# 004-H-01.net
KiCad netlist of a schematic drawn in Altium Designer
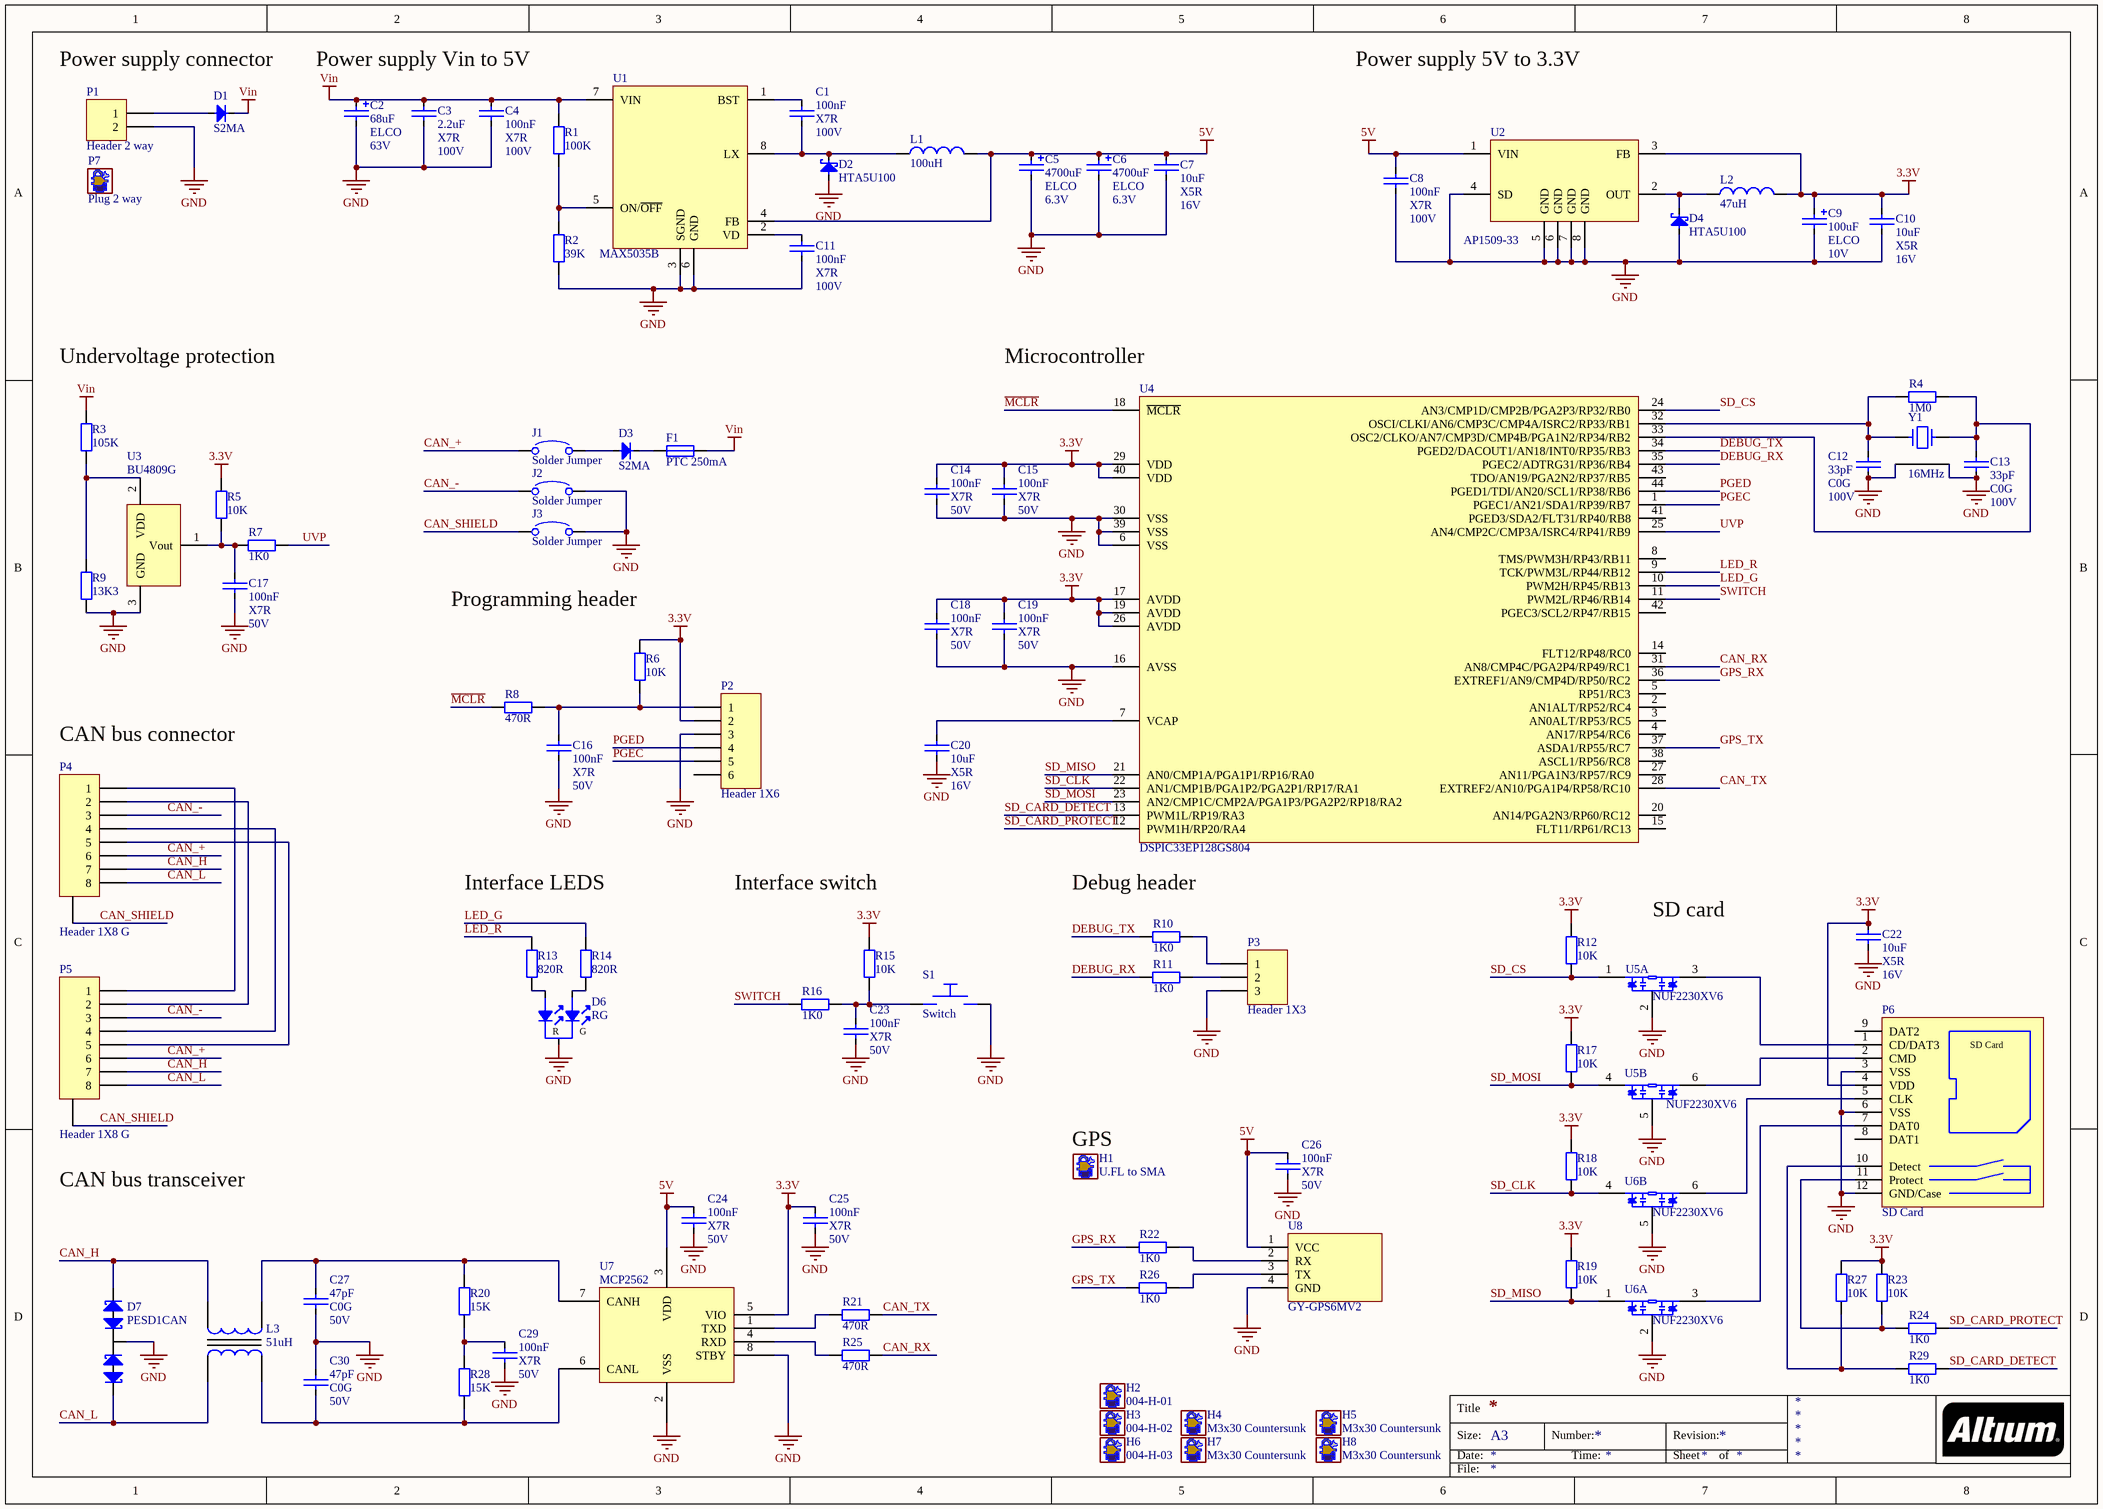
[diagram p0: 004-H-01.SchDoc]

(export (version "E")
  (design (tool "Eeschema 10.0.6"))
  (components
    (comp (ref "C1")
      (value "100nF")
      (footprint "CAP0805")
      (description "Capacitor")
      (fields (field (name "DIELECTRIC") "X7R") (field (name "VOLTAGERATING") "100V"))
      (libsource (lib "004-H-01") (part "Capacitor"))
    )
    (comp (ref "C2")
      (value "68uF")
      (footprint "CAPP8383X62N")
      (description "Capacitor Pol")
      (fields
        (field (name "MANUFACTURER") "Panasonic")
        (field (name "MANUFACTURER PART NO") "EEEFK1J680UP")
        (field (name "DIELECTRIC") "ELCO")
        (field (name "VOLTAGERATING") "63V")
      )
      (libsource (lib "004-H-01") (part "CapacitorPol"))
    )
    (comp (ref "C3")
      (value "2.2uF")
      (footprint "CAP1210")
      (description "Capacitor")
      (fields
        (field (name "MANUFACTURER") "AVX")
        (field (name "MANUFACTURER PART NO") "C1210X225K1RACTU")
        (field (name "DIELECTRIC") "X7R")
        (field (name "VOLTAGERATING") "100V")
      )
      (libsource (lib "ProtoBoard") (part "Capacitor"))
    )
    (comp (ref "C4")
      (value "100nF")
      (footprint "CAP0805")
      (description "Capacitor")
      (fields (field (name "DIELECTRIC") "X7R") (field (name "VOLTAGERATING") "100V"))
      (libsource (lib "ProtoBoard") (part "Capacitor"))
    )
    (comp (ref "C5")
      (value "4700uF")
      (footprint "CAPPOL_leaded_D12_5L20P5")
      (description "Capacitor Pol")
      (fields
        (field (name "MANUFACTURER") "Panasonic")
        (field (name "MANUFACTURER PART NO") "ECA0JM472")
        (field (name "DIELECTRIC") "ELCO")
        (field (name "VOLTAGERATING") "6.3V")
      )
      (libsource (lib "004-H-01") (part "CapacitorPol"))
    )
    (comp (ref "C6")
      (value "4700uF")
      (footprint "CAPPOL_leaded_D12_5L20P5")
      (description "Capacitor Pol")
      (fields
        (field (name "MANUFACTURER") "Panasonic")
        (field (name "MANUFACTURER PART NO") "ECA0JM472")
        (field (name "DIELECTRIC") "ELCO")
        (field (name "VOLTAGERATING") "6.3V")
      )
      (libsource (lib "004-H-01") (part "CapacitorPol"))
    )
    (comp (ref "C7")
      (value "10uF")
      (footprint "CAP1210")
      (description "Capacitor")
      (fields
        (field (name "MANUFACTURER") "Multicomp")
        (field (name "MANUFACTURER PART NO") "MC1210X106K160CT")
        (field (name "DIELECTRIC") "X5R")
        (field (name "VOLTAGERATING") "16V")
      )
      (libsource (lib "ProtoBoard") (part "Capacitor"))
    )
    (comp (ref "C8")
      (value "100nF")
      (footprint "CAP0805")
      (description "Capacitor")
      (fields (field (name "DIELECTRIC") "X7R") (field (name "VOLTAGERATING") "100V"))
      (libsource (lib "004-H-01") (part "Capacitor"))
    )
    (comp (ref "C9")
      (value "100uF")
      (footprint "CAPP8383X62N")
      (description "Capacitor Pol")
      (fields
        (field (name "MANUFACTURER") "Panasonic")
        (field (name "MANUFACTURER PART NO") "EEEHA1A101P")
        (field (name "DIELECTRIC") "ELCO")
        (field (name "VOLTAGERATING") "10V")
      )
      (libsource (lib "004-H-01") (part "CapacitorPol"))
    )
    (comp (ref "C10")
      (value "10uF")
      (footprint "CAP1210")
      (description "Capacitor")
      (fields
        (field (name "MANUFACTURER") "Multicomp")
        (field (name "MANUFACTURER PART NO") "MC1210X106K160CT")
        (field (name "DIELECTRIC") "X5R")
        (field (name "VOLTAGERATING") "16V")
      )
      (libsource (lib "ProtoBoard") (part "Capacitor"))
    )
    (comp (ref "C11")
      (value "100nF")
      (footprint "CAP0805")
      (description "Capacitor")
      (fields (field (name "DIELECTRIC") "X7R") (field (name "VOLTAGERATING") "100V"))
      (libsource (lib "004-H-01") (part "Capacitor"))
    )
    (comp (ref "C12")
      (value "33pF")
      (footprint "CAP0603")
      (description "Capacitor")
      (fields (field (name "DIELECTRIC") "C0G") (field (name "VOLTAGERATING") "100V"))
      (libsource (lib "ProtoBoard") (part "Capacitor"))
    )
    (comp (ref "C13")
      (value "33pF")
      (footprint "CAP0603")
      (description "Capacitor")
      (fields (field (name "DIELECTRIC") "C0G") (field (name "VOLTAGERATING") "100V"))
      (libsource (lib "ProtoBoard") (part "Capacitor"))
    )
    (comp (ref "C14")
      (value "100nF")
      (footprint "CAP0603")
      (description "Capacitor")
      (fields (field (name "DIELECTRIC") "X7R") (field (name "VOLTAGERATING") "50V"))
      (libsource (lib "004-H-01") (part "Capacitor"))
    )
    (comp (ref "C15")
      (value "100nF")
      (footprint "CAP0603")
      (description "Capacitor")
      (fields (field (name "DIELECTRIC") "X7R") (field (name "VOLTAGERATING") "50V"))
      (libsource (lib "004-H-01") (part "Capacitor"))
    )
    (comp (ref "C16")
      (value "100nF")
      (footprint "CAP0603")
      (description "Capacitor")
      (fields (field (name "DIELECTRIC") "X7R") (field (name "VOLTAGERATING") "50V"))
      (libsource (lib "ProtoBoard") (part "Capacitor"))
    )
    (comp (ref "C17")
      (value "100nF")
      (footprint "CAP0603")
      (description "Capacitor")
      (fields (field (name "DIELECTRIC") "X7R") (field (name "VOLTAGERATING") "50V"))
      (libsource (lib "ProtoBoard") (part "Capacitor"))
    )
    (comp (ref "C18")
      (value "100nF")
      (footprint "CAP0603")
      (description "Capacitor")
      (fields (field (name "DIELECTRIC") "X7R") (field (name "VOLTAGERATING") "50V"))
      (libsource (lib "004-H-01") (part "Capacitor"))
    )
    (comp (ref "C19")
      (value "100nF")
      (footprint "CAP0603")
      (description "Capacitor")
      (fields (field (name "DIELECTRIC") "X7R") (field (name "VOLTAGERATING") "50V"))
      (libsource (lib "004-H-01") (part "Capacitor"))
    )
    (comp (ref "C20")
      (value "10uF")
      (footprint "CAP1210")
      (description "Capacitor")
      (fields
        (field (name "MANUFACTURER") "Multicomp")
        (field (name "MANUFACTURER PART NO") "MC1210X106K160CT")
        (field (name "DIELECTRIC") "X5R")
        (field (name "VOLTAGERATING") "16V")
      )
      (libsource (lib "ProtoBoard") (part "Capacitor"))
    )
    (comp (ref "C22")
      (value "10uF")
      (footprint "CAP1210")
      (description "Capacitor")
      (fields
        (field (name "MANUFACTURER") "Multicomp")
        (field (name "MANUFACTURER PART NO") "MC1210X106K160CT")
        (field (name "DIELECTRIC") "X5R")
        (field (name "VOLTAGERATING") "16V")
      )
      (libsource (lib "ProtoBoard") (part "Capacitor"))
    )
    (comp (ref "C23")
      (value "100nF")
      (footprint "CAP0603")
      (description "Capacitor")
      (fields (field (name "DIELECTRIC") "X7R") (field (name "VOLTAGERATING") "50V"))
      (libsource (lib "004-H-01") (part "Capacitor"))
    )
    (comp (ref "C24")
      (value "100nF")
      (footprint "CAP0603")
      (description "Capacitor")
      (fields (field (name "DIELECTRIC") "X7R") (field (name "VOLTAGERATING") "50V"))
      (libsource (lib "004-H-01") (part "Capacitor"))
    )
    (comp (ref "C25")
      (value "100nF")
      (footprint "CAP0603")
      (description "Capacitor")
      (fields (field (name "DIELECTRIC") "X7R") (field (name "VOLTAGERATING") "50V"))
      (libsource (lib "004-H-01") (part "Capacitor"))
    )
    (comp (ref "C26")
      (value "100nF")
      (footprint "CAP0603")
      (description "Capacitor")
      (fields (field (name "DIELECTRIC") "X7R") (field (name "VOLTAGERATING") "50V"))
      (libsource (lib "004-H-01") (part "Capacitor"))
    )
    (comp (ref "C27")
      (value "47pF")
      (footprint "CAP0603")
      (description "Capacitor")
      (fields (field (name "DIELECTRIC") "C0G") (field (name "VOLTAGERATING") "50V"))
      (libsource (lib "ProtoBoard") (part "Capacitor"))
    )
    (comp (ref "C29")
      (value "100nF")
      (footprint "CAP0603")
      (description "Capacitor")
      (fields (field (name "DIELECTRIC") "X7R") (field (name "VOLTAGERATING") "50V"))
      (libsource (lib "004-H-01") (part "Capacitor"))
    )
    (comp (ref "C30")
      (value "47pF")
      (footprint "CAP0603")
      (description "Capacitor")
      (fields (field (name "DIELECTRIC") "C0G") (field (name "VOLTAGERATING") "50V"))
      (libsource (lib "ProtoBoard") (part "Capacitor"))
    )
    (comp (ref "D1")
      (value "S2MA")
      (footprint "DIODEDO-214AC")
      (description "Diode")
      (fields (field (name "MANUFACTURER") "Multicomp"))
      (libsource (lib "004-H-01") (part "Diode"))
    )
    (comp (ref "D2")
      (value "HTA5U100")
      (footprint "DIODEDO-214AC")
      (description "Diode Schottky")
      (fields (field (name "MANUFACTURER") "Multicomp"))
      (libsource (lib "ProtoBoard") (part "Diode Schottky"))
    )
    (comp (ref "D3")
      (value "S2MA")
      (footprint "DIODEDO-214AC")
      (description "Diode")
      (fields (field (name "MANUFACTURER") "Multicomp"))
      (libsource (lib "004-H-01") (part "Diode"))
    )
    (comp (ref "D4")
      (value "HTA5U100")
      (footprint "DIODEDO-214AC")
      (description "Diode Schottky")
      (fields (field (name "MANUFACTURER") "Multicomp"))
      (libsource (lib "ProtoBoard") (part "Diode Schottky"))
    )
    (comp (ref "D6")
      (value "RG")
      (footprint "LED_RG_COMMON_GND")
      (description "Led RG")
      (fields (field (name "MANUFACTURER") "Multicomp") (field (name "MANUFACTURER PART NO") "MCL039PURGW"))
      (libsource (lib "004-H-01") (part "Led_RG_Common_GND"))
    )
    (comp (ref "D7")
      (value "PESD1CAN")
      (footprint "SOT23-3N")
      (description "ESD Protection Device, TVS, 70 V, SOT-23, 3 Pins")
      (fields (field (name "MANUFACTURER") "NXP"))
      (libsource (lib "ProtoBoard") (part "PESD1CAN"))
    )
    (comp (ref "F1")
      (value "PTC 250mA")
      (footprint "Fuse1210")
      (description "Fuse")
      (fields (field (name "MANUFACTURER") "Bel Fuse") (field (name "MANUFACTURER PART NO") "0ZCH0010FF2E"))
      (libsource (lib "004-H-01") (part "Fuse"))
    )
    (comp (ref "H1")
      (value "U.FL to SMA")
      (description "RF / Coaxial Cable Assembly, U.FL Jack to SMA Bulkhead Jack, 50 ohm, 0.25 ft, 75 mm")
      (fields
        (field (name "MANUFACTURER") "RF SOLUTIONS")
        (field (name "MANUFACTURER PART NO") "CBA-UFLSMA-1")
      )
      (libsource (lib "004-H-01") (part "Hardware"))
    )
    (comp (ref "H2") (value "004-H-01") (description "PCB") (libsource (lib "004-H-01") (part "Hardware")))
    (comp (ref "H3")
      (value "004-H-02")
      (description "Casing bottom")
      (libsource (lib "004-H-01") (part "Hardware"))
    )
    (comp (ref "H4")
      (value "M3x30 Countersunk")
      (description "M3x30 Xountersunk Bolt")
      (libsource (lib "004-H-01") (part "Hardware"))
    )
    (comp (ref "H5")
      (value "M3x30 Countersunk")
      (description "M3x30 Xountersunk Bolt")
      (libsource (lib "004-H-01") (part "Hardware"))
    )
    (comp (ref "H6")
      (value "004-H-03")
      (description "Casing top")
      (libsource (lib "004-H-01") (part "Hardware"))
    )
    (comp (ref "H7")
      (value "M3x30 Countersunk")
      (description "M3x30 Xountersunk Bolt")
      (libsource (lib "004-H-01") (part "Hardware"))
    )
    (comp (ref "H8")
      (value "M3x30 Countersunk")
      (description "M3x30 Xountersunk Bolt")
      (libsource (lib "004-H-01") (part "Hardware"))
    )
    (comp (ref "J1")
      (value "Solder Jumper")
      (footprint "SolderJumer")
      (description "Solder jumper open")
      (libsource (lib "004-H-01") (part "SolderJumper"))
    )
    (comp (ref "J2")
      (value "Solder Jumper")
      (footprint "SolderJumer")
      (description "Solder jumper open")
      (libsource (lib "004-H-01") (part "SolderJumper"))
    )
    (comp (ref "J3")
      (value "Solder Jumper")
      (footprint "SolderJumer")
      (description "Solder jumper open")
      (libsource (lib "004-H-01") (part "SolderJumper"))
    )
    (comp (ref "L1")
      (value "100uH")
      (footprint "INDP3030X28N")
      (description "Inductor")
      (fields (field (name "MANUFACTURER") "BOURNS") (field (name "MANUFACTURER PART NO") "SDR0302-101KL"))
      (libsource (lib "altium-import") (part "root_0_Inductor_"))
    )
    (comp (ref "L2")
      (value "47uH")
      (footprint "INDP3030X28N")
      (description "Inductor")
      (fields (field (name "MANUFACTURER") "Bourns") (field (name "MANUFACTURER PART NO") "SDR0302-470KL"))
      (libsource (lib "altium-import") (part "root_0_Inductor_"))
    )
    (comp (ref "L3")
      (value "51uH")
      (footprint "IND200P450X300-4N")
      (description "Choke common mode")
      (fields (field (name "MANUFACTURER") "Bourns") (field (name "MANUFACTURER PART NO") "SRF4532-510Y"))
      (libsource (lib "ProtoBoard") (part "Choke Common Mode"))
    )
    (comp (ref "P1")
      (value "Header 2 way")
      (footprint "21.95MH/2-E")
      (fields
        (field (name "MANUFACTURER") "IMO PRECISION CONTROLS")
        (field (name "MANUFACTURER PART NO") "21.95MH/2-E")
      )
      (libsource (lib "004-H-01") (part "Header1X2"))
    )
    (comp (ref "P2")
      (value "Header 1X6")
      (footprint "Header1X6P100")
      (description "Connector 1X6")
      (fields (field (name "MANUFACTURER") "Multicomp") (field (name "MANUFACTURER PART NO") "2211S-06G"))
      (libsource (lib "ProtoBoard") (part "Header1X6"))
    )
    (comp (ref "P3")
      (value "Header 1X3")
      (footprint "Header1X3P100")
      (description "Connector 1X3")
      (fields (field (name "MANUFACTURER") "Multicomp") (field (name "MANUFACTURER PART NO") "2211S-03G"))
      (libsource (lib "ProtoBoard") (part "Header1X3"))
    )
    (comp (ref "P4")
      (value "Header 1X8 G")
      (footprint "TECO-1-406541-5")
      (description "Connector 1X8 with Ground")
      (fields
        (field (name "MANUFACTURER") "TE CONNECTIVITY")
        (field (name "MANUFACTURER PART NO") "1-406541-5")
      )
      (libsource (lib "004-H-01") (part "Header1X8+G"))
    )
    (comp (ref "P5")
      (value "Header 1X8 G")
      (footprint "TECO-1-406541-5")
      (description "Connector 1X8 with Ground")
      (fields
        (field (name "MANUFACTURER") "TE CONNECTIVITY")
        (field (name "MANUFACTURER PART NO") "1-406541-5")
      )
      (libsource (lib "004-H-01") (part "Header1X8+G"))
    )
    (comp (ref "P6")
      (value "SD Card")
      (footprint "SDK-9BNS-K13-GS-TB")
      (description "SD slot connector with card detect and protect")
      (fields (field (name "MANUFACTURER") "JST") (field (name "MANUFACTURER PART NO") "SDK-9BNS-K13-GS-TB"))
      (libsource (lib "004-H-01") (part "SD slot"))
    )
    (comp (ref "P7")
      (value "Plug 2 way")
      (description "Generaric hardware")
      (fields
        (field (name "MANUFACTURER") "IMO PRECISION CONTROLS")
        (field (name "MANUFACTURER PART NO") "21.950M/2-E")
      )
      (libsource (lib "004-H-01") (part "Hardware"))
    )
    (comp (ref "R1")
      (value "100K")
      (footprint "RES0805")
      (description "Resistor")
      (fields (field (name "TOLERANCE") "1%"))
      (libsource (lib "") (part "Resistor_1"))
    )
    (comp (ref "R2")
      (value "39K")
      (footprint "RES0805")
      (description "Resistor")
      (fields (field (name "TOLERANCE") "1%"))
      (libsource (lib "") (part "Resistor_1"))
    )
    (comp (ref "R3")
      (value "105K")
      (footprint "RES0805")
      (description "Resistor")
      (fields (field (name "TOLERANCE") "1%"))
      (libsource (lib "") (part "Resistor_1"))
    )
    (comp (ref "R4")
      (value "1M0")
      (footprint "RES0603")
      (description "Resistor")
      (fields (field (name "TOLERANCE") "1%"))
      (libsource (lib "") (part "Resistor_1"))
    )
    (comp (ref "R5")
      (value "10K")
      (footprint "RES0603")
      (description "Resistor")
      (fields (field (name "TOLERANCE") "1%"))
      (libsource (lib "") (part "Resistor_1"))
    )
    (comp (ref "R6")
      (value "10K")
      (footprint "RES0603")
      (description "Resistor")
      (fields (field (name "TOLERANCE") "1%"))
      (libsource (lib "ProtoBoard") (part "Resistor"))
    )
    (comp (ref "R7")
      (value "1K0")
      (footprint "RES0603")
      (description "Resistor")
      (fields (field (name "TOLERANCE") "1%"))
      (libsource (lib "004-H-01") (part "Resistor"))
    )
    (comp (ref "R8")
      (value "470R")
      (footprint "RES0603")
      (description "Resistor")
      (fields (field (name "TOLERANCE") "1%"))
      (libsource (lib "") (part "Resistor_1"))
    )
    (comp (ref "R9")
      (value "13K3")
      (footprint "RES0805")
      (description "Resistor")
      (fields (field (name "TOLERANCE") "1%"))
      (libsource (lib "") (part "Resistor_1"))
    )
    (comp (ref "R10")
      (value "1K0")
      (footprint "RES0603")
      (description "Resistor")
      (fields (field (name "TOLERANCE") "1%"))
      (libsource (lib "") (part "Resistor_1"))
    )
    (comp (ref "R11")
      (value "1K0")
      (footprint "RES0603")
      (description "Resistor")
      (fields (field (name "TOLERANCE") "1%"))
      (libsource (lib "") (part "Resistor_1"))
    )
    (comp (ref "R12")
      (value "10K")
      (footprint "RES0603")
      (description "Resistor")
      (fields (field (name "TOLERANCE") "1%"))
      (libsource (lib "") (part "Resistor_1"))
    )
    (comp (ref "R13")
      (value "820R")
      (footprint "RES0603")
      (description "Resistor")
      (fields (field (name "TOLERANCE") "1%"))
      (libsource (lib "002-H-01") (part "Resistor"))
    )
    (comp (ref "R14")
      (value "820R")
      (footprint "RES0603")
      (description "Resistor")
      (fields (field (name "TOLERANCE") "1%"))
      (libsource (lib "002-H-01") (part "Resistor"))
    )
    (comp (ref "R15")
      (value "10K")
      (footprint "RES0603")
      (description "Resistor")
      (fields (field (name "TOLERANCE") "1%"))
      (libsource (lib "") (part "Resistor_1"))
    )
    (comp (ref "R16")
      (value "1K0")
      (footprint "RES0603")
      (description "Resistor")
      (fields (field (name "TOLERANCE") "1%"))
      (libsource (lib "004-H-01") (part "Resistor"))
    )
    (comp (ref "R17")
      (value "10K")
      (footprint "RES0603")
      (description "Resistor")
      (fields (field (name "TOLERANCE") "1%"))
      (libsource (lib "") (part "Resistor_1"))
    )
    (comp (ref "R18")
      (value "10K")
      (footprint "RES0603")
      (description "Resistor")
      (fields (field (name "TOLERANCE") "1%"))
      (libsource (lib "") (part "Resistor_1"))
    )
    (comp (ref "R19")
      (value "10K")
      (footprint "RES0603")
      (description "Resistor")
      (fields (field (name "TOLERANCE") "1%"))
      (libsource (lib "") (part "Resistor_1"))
    )
    (comp (ref "R20")
      (value "15K")
      (footprint "RES0603")
      (description "Resistor")
      (fields (field (name "TOLERANCE") "1%"))
      (libsource (lib "ProtoBoard") (part "Resistor"))
    )
    (comp (ref "R21")
      (value "470R")
      (footprint "RES0603")
      (description "Resistor")
      (fields (field (name "TOLERANCE") "1%"))
      (libsource (lib "") (part "Resistor_1"))
    )
    (comp (ref "R22")
      (value "1K0")
      (footprint "RES0603")
      (description "Resistor")
      (fields (field (name "TOLERANCE") "1%"))
      (libsource (lib "004-H-01") (part "Resistor"))
    )
    (comp (ref "R23")
      (value "10K")
      (footprint "RES0603")
      (description "Resistor")
      (fields (field (name "TOLERANCE") "1%"))
      (libsource (lib "") (part "Resistor_1"))
    )
    (comp (ref "R24")
      (value "1K0")
      (footprint "RES0603")
      (description "Resistor")
      (fields (field (name "TOLERANCE") "1%"))
      (libsource (lib "004-H-01") (part "Resistor"))
    )
    (comp (ref "R25")
      (value "470R")
      (footprint "RES0603")
      (description "Resistor")
      (fields (field (name "TOLERANCE") "1%"))
      (libsource (lib "") (part "Resistor_1"))
    )
    (comp (ref "R26")
      (value "1K0")
      (footprint "RES0603")
      (description "Resistor")
      (fields (field (name "TOLERANCE") "1%"))
      (libsource (lib "004-H-01") (part "Resistor"))
    )
    (comp (ref "R27")
      (value "10K")
      (footprint "RES0603")
      (description "Resistor")
      (fields (field (name "TOLERANCE") "1%"))
      (libsource (lib "") (part "Resistor_1"))
    )
    (comp (ref "R28")
      (value "15K")
      (footprint "RES0603")
      (description "Resistor")
      (fields (field (name "TOLERANCE") "1%"))
      (libsource (lib "ProtoBoard") (part "Resistor"))
    )
    (comp (ref "R29")
      (value "1K0")
      (footprint "RES0603")
      (description "Resistor")
      (fields (field (name "TOLERANCE") "1%"))
      (libsource (lib "004-H-01") (part "Resistor"))
    )
    (comp (ref "S1")
      (value "Switch")
      (footprint "FSMRA4JH")
      (description "Tactile Switch")
      (fields
        (field (name "MANUFACTURER") "TE CONNECTIVITY")
        (field (name "MANUFACTURER PART NO") "FSMRA4JH")
      )
      (libsource (lib "004-H-01") (part "TactileSwitch"))
    )
    (comp (ref "U1")
      (value "MAX5035B")
      (footprint "SOIC-8N")
      (description "5V 1A, 76V, High-Efficiency MAXPower Step-Down DC-DC Converter")
      (fields
        (field (name "MANUFACTURER") "Maxim Integrated Products")
        (field (name "MANUFACTURER PART NO") "MAX5035BUSA+T")
      )
      (libsource (lib "004-H-01") (part "MAX5035B"))
    )
    (comp (ref "U2")
      (value "AP1509-33")
      (footprint "SOIC-8N")
      (description "150KHz, 2A PWM BUCK DC/DC CONVERTER")
      (fields
        (field (name "MANUFACTURER") "Diodes Inc")
        (field (name "MANUFACTURER PART NO") "AP1509-33SG-13")
      )
      (libsource (lib "ProtoBoard") (part "AP1509-33"))
    )
    (comp (ref "U3")
      (value "BU4809G")
      (footprint "SOT95P280X125-5N")
      (description "Voltage Detector")
      (fields (field (name "MANUFACTURER") "ROHM") (field (name "MANUFACTURER PART NO") "BU4809G-TR"))
      (libsource (lib "004-H-01") (part "BD48xx"))
    )
    (comp (ref "U4")
      (value "DSPIC33EP128GS804")
      (footprint "TQFP80P1200X1200X120-44N")
      (fields
        (field (name "MANUFACTURER") "Microchip")
        (field (name "MANUFACTURER PART NO") "DSPIC33EP128GS804-I/PT")
      )
      (libsource (lib "ProtoBoard") (part "DSPIC33EP128GS804"))
    )
    (comp (ref "U5")
      (value "NUF2230XV6")
      (footprint "SOT50P160X60-6N")
      (description "2 Line EMI Filter with ESDProtection")
      (fields
        (field (name "MANUFACTURER") "ON SEMICONDUCTOR")
        (field (name "MANUFACTURER PART NO") "NUF2230XV6T1G")
      )
      (libsource (lib "004-H-01") (part "NUF2230XV6"))
    )
    (comp (ref "U6")
      (value "NUF2230XV6")
      (footprint "SOT50P160X60-6N")
      (description "2 Line EMI Filter with ESDProtection")
      (fields
        (field (name "MANUFACTURER") "ON SEMICONDUCTOR")
        (field (name "MANUFACTURER PART NO") "NUF2230XV6T1G")
      )
      (libsource (lib "004-H-01") (part "NUF2230XV6"))
    )
    (comp (ref "U7")
      (value "MCP2562")
      (footprint "SOIC-8N")
      (description "CAN Bus, Transceiver, CAN, LIN, 1, 1, 4.5 V, 5.5 V, SOIC")
      (fields (field (name "MANUFACTURER") "Microchip") (field (name "MANUFACTURER PART NO") "MCP2562-E/SN"))
      (libsource (lib "ProtoBoard") (part "MCP2562"))
    )
    (comp (ref "U8")
      (value "GY-GPS6MV2")
      (footprint "GY-GPS6MV2")
      (description "GPS module")
      (fields (field (name "MANUFACTURER") "Ebay") (field (name "MANUFACTURER PART NO") "GY-NEO6MV2"))
      (libsource (lib "004-H-01") (part "GY-GPS6MV2"))
    )
    (comp (ref "Y1")
      (value "16MHz")
      (footprint "CrystalSMD 5032")
      (description "Crystal")
      (fields
        (field (name "MANUFACTURER") "MULTICOMP")
        (field (name "MANUFACTURER PART NO") "MCSJK-7I-16.00-18-30-60-B-30")
      )
      (libsource (lib "004-H-01") (part "Crystal_1"))
    )
  )
  (nets
    (net (code "1") (name "/CAN_+") (class "Default")
      (node (ref "J1") (pin "1") (pinfunction "1_1") (pintype "passive"))
      (node (ref "P4") (pin "6") (pinfunction "6_6") (pintype "passive"))
      (node (ref "P5") (pin "6") (pinfunction "6_6") (pintype "passive"))
    )
    (net (code "2") (name "/CAN_-") (class "Default")
      (node (ref "J2") (pin "1") (pinfunction "1_1") (pintype "passive"))
      (node (ref "P4") (pin "3") (pinfunction "3_3") (pintype "passive"))
      (node (ref "P5") (pin "3") (pinfunction "3_3") (pintype "passive"))
    )
    (net (code "3") (name "/CAN_H") (class "Default")
      (node (ref "D7") (pin "1") (pinfunction "1_1") (pintype "passive"))
      (node (ref "L3") (pin "4") (pinfunction "4_4") (pintype "passive"))
      (node (ref "P4") (pin "7") (pinfunction "7_7") (pintype "passive"))
      (node (ref "P5") (pin "7") (pinfunction "7_7") (pintype "passive"))
    )
    (net (code "4") (name "/CAN_L") (class "Default")
      (node (ref "D7") (pin "2") (pinfunction "2_2") (pintype "passive"))
      (node (ref "L3") (pin "1") (pinfunction "1_1") (pintype "passive"))
      (node (ref "P4") (pin "8") (pinfunction "8_8") (pintype "passive"))
      (node (ref "P5") (pin "8") (pinfunction "8_8") (pintype "passive"))
    )
    (net (code "5") (name "/CAN_RX") (class "Default")
      (node (ref "R25") (pin "2") (pinfunction "2_2") (pintype "passive"))
      (node (ref "U4") (pin "31") (pinfunction "AN8/CMP4C/PGA2P4/RP49/RC1_31") (pintype "passive"))
    )
    (net (code "6") (name "/CAN_SHIELD") (class "Default")
      (node (ref "J3") (pin "1") (pinfunction "1_1") (pintype "passive"))
      (node (ref "P4") (pin "9") (pinfunction "G_9") (pintype "passive"))
      (node (ref "P5") (pin "9") (pinfunction "G_9") (pintype "passive"))
    )
    (net (code "7") (name "/CAN_TX") (class "Default")
      (node (ref "R21") (pin "2") (pinfunction "2_2") (pintype "passive"))
      (node (ref "U4") (pin "28") (pinfunction "EXTREF2/AN10/PGA1P4/RP58/RC10_28") (pintype "passive"))
    )
    (net (code "8") (name "/DEBUG_RX") (class "Default")
      (node (ref "R11") (pin "1") (pinfunction "1_1") (pintype "passive"))
      (node (ref "U4") (pin "35") (pinfunction "PGEC2/ADTRG31/RP36/RB4_35") (pintype "passive"))
    )
    (net (code "9") (name "/DEBUG_TX") (class "Default")
      (node (ref "R10") (pin "1") (pinfunction "1_1") (pintype "passive"))
      (node (ref "U4") (pin "34") (pinfunction "PGED2/DACOUT1/AN18/INT0/RP35/RB3_34") (pintype "passive"))
    )
    (net (code "10") (name "/GPS_RX") (class "Default")
      (node (ref "R22") (pin "1") (pinfunction "1_1") (pintype "passive"))
      (node (ref "U4") (pin "36") (pinfunction "EXTREF1/AN9/CMP4D/RP50/RC2_36") (pintype "passive"))
    )
    (net (code "11") (name "/GPS_TX") (class "Default")
      (node (ref "R26") (pin "1") (pinfunction "1_1") (pintype "passive"))
      (node (ref "U4") (pin "37") (pinfunction "ASDA1/RP55/RC7_37") (pintype "passive"))
    )
    (net (code "12") (name "/LED_G") (class "Default")
      (node (ref "R14") (pin "1") (pinfunction "1_1") (pintype "passive"))
      (node (ref "U4") (pin "10") (pinfunction "PWM2H/RP45/RB13_10") (pintype "passive"))
    )
    (net (code "13") (name "/LED_R") (class "Default")
      (node (ref "R13") (pin "1") (pinfunction "1_1") (pintype "passive"))
      (node (ref "U4") (pin "9") (pinfunction "TCK/PWM3L/RP44/RB12_9") (pintype "passive"))
    )
    (net (code "14") (name "/PGEC") (class "Default")
      (node (ref "P2") (pin "5") (pinfunction "5_5") (pintype "passive"))
      (node (ref "U4") (pin "1") (pinfunction "PGEC1/AN21/SDA1/RP39/RB7_1") (pintype "passive"))
    )
    (net (code "15") (name "/PGED") (class "Default")
      (node (ref "P2") (pin "4") (pinfunction "4_4") (pintype "passive"))
      (node (ref "U4") (pin "44") (pinfunction "PGED1/TDI/AN20/SCL1/RP38/RB6_44") (pintype "passive"))
    )
    (net (code "16") (name "/SD_CARD_DETECT") (class "Default")
      (node (ref "R29") (pin "2") (pinfunction "2_2") (pintype "passive"))
      (node (ref "U4") (pin "13") (pinfunction "PWM1L/RP19/RA3_13") (pintype "passive"))
    )
    (net (code "17") (name "/SD_CARD_PROTECT") (class "Default")
      (node (ref "R24") (pin "2") (pinfunction "2_2") (pintype "passive"))
      (node (ref "U4") (pin "12") (pinfunction "PWM1H/RP20/RA4_12") (pintype "passive"))
    )
    (net (code "18") (name "/SD_CLK") (class "Default")
      (node (ref "R18") (pin "2") (pinfunction "2_2") (pintype "passive"))
      (node (ref "U4") (pin "22") (pinfunction "AN1/CMP1B/PGA1P2/PGA2P1/RP17/RA1_22") (pintype "passive"))
      (node (ref "U6") (pin "4") (pinfunction "4_4") (pintype "passive"))
    )
    (net (code "19") (name "/SD_CS") (class "Default")
      (node (ref "R12") (pin "2") (pinfunction "2_2") (pintype "passive"))
      (node (ref "U4") (pin "24") (pinfunction "AN3/CMP1D/CMP2B/PGA2P3/RP32/RB0_24") (pintype "passive"))
      (node (ref "U5") (pin "1") (pinfunction "1_1") (pintype "passive"))
    )
    (net (code "20") (name "/SD_MISO") (class "Default")
      (node (ref "R19") (pin "2") (pinfunction "2_2") (pintype "passive"))
      (node (ref "U4") (pin "21") (pinfunction "AN0/CMP1A/PGA1P1/RP16/RA0_21") (pintype "passive"))
      (node (ref "U6") (pin "1") (pinfunction "1_1") (pintype "passive"))
    )
    (net (code "21") (name "/SD_MOSI") (class "Default")
      (node (ref "R17") (pin "2") (pinfunction "2_2") (pintype "passive"))
      (node (ref "U4") (pin "23") (pinfunction "AN2/CMP1C/CMP2A/PGA1P3/PGA2P2/RP18/RA2_23") (pintype "passive"))
      (node (ref "U5") (pin "4") (pinfunction "4_4") (pintype "passive"))
    )
    (net (code "22") (name "/SWITCH") (class "Default")
      (node (ref "R16") (pin "1") (pinfunction "1_1") (pintype "passive"))
      (node (ref "U4") (pin "11") (pinfunction "PWM2L/RP46/RB14_11") (pintype "passive"))
    )
    (net (code "23") (name "/UVP") (class "Default")
      (node (ref "R7") (pin "2") (pinfunction "2_2") (pintype "passive"))
      (node (ref "U4") (pin "25") (pinfunction "AN4/CMP2C/CMP3A/ISRC4/RP41/RB9_25") (pintype "passive"))
    )
    (net (code "24") (name "/~{MCLR}") (class "Default")
      (node (ref "R8") (pin "1") (pinfunction "1_1") (pintype "passive"))
      (node (ref "U4") (pin "18") (pinfunction "~{MCLR}_18") (pintype "passive"))
    )
    (net (code "25") (name "3.3V") (class "Default")
      (node (ref "C10") (pin "2") (pinfunction "2_2") (pintype "passive"))
      (node (ref "C14") (pin "2") (pinfunction "2_2") (pintype "passive"))
      (node (ref "C15") (pin "2") (pinfunction "2_2") (pintype "passive"))
      (node (ref "C18") (pin "2") (pinfunction "2_2") (pintype "passive"))
      (node (ref "C19") (pin "2") (pinfunction "2_2") (pintype "passive"))
      (node (ref "C22") (pin "2") (pinfunction "2_2") (pintype "passive"))
      (node (ref "C25") (pin "2") (pinfunction "2_2") (pintype "passive"))
      (node (ref "C9") (pin "1") (pinfunction "1_1") (pintype "passive"))
      (node (ref "L2") (pin "2") (pinfunction "2_2") (pintype "passive"))
      (node (ref "P2") (pin "2") (pinfunction "2_2") (pintype "passive"))
      (node (ref "P6") (pin "4") (pinfunction "VDD_4") (pintype "passive"))
      (node (ref "R12") (pin "1") (pinfunction "1_1") (pintype "passive"))
      (node (ref "R15") (pin "1") (pinfunction "1_1") (pintype "passive"))
      (node (ref "R17") (pin "1") (pinfunction "1_1") (pintype "passive"))
      (node (ref "R18") (pin "1") (pinfunction "1_1") (pintype "passive"))
      (node (ref "R19") (pin "1") (pinfunction "1_1") (pintype "passive"))
      (node (ref "R23") (pin "1") (pinfunction "1_1") (pintype "passive"))
      (node (ref "R27") (pin "1") (pinfunction "1_1") (pintype "passive"))
      (node (ref "R5") (pin "1") (pinfunction "1_1") (pintype "passive"))
      (node (ref "R6") (pin "1") (pinfunction "1_1") (pintype "passive"))
      (node (ref "U2") (pin "3") (pinfunction "FB_3") (pintype "passive"))
      (node (ref "U4") (pin "17") (pinfunction "AVDD_17") (pintype "passive"))
      (node (ref "U4") (pin "19") (pinfunction "AVDD_19") (pintype "passive"))
      (node (ref "U4") (pin "26") (pinfunction "AVDD_26") (pintype "passive"))
      (node (ref "U4") (pin "29") (pinfunction "VDD_29") (pintype "passive"))
      (node (ref "U4") (pin "40") (pinfunction "VDD_40") (pintype "passive"))
      (node (ref "U7") (pin "5") (pinfunction "VIO_5") (pintype "passive"))
    )
    (net (code "26") (name "5V") (class "Default")
      (node (ref "C24") (pin "2") (pinfunction "2_2") (pintype "passive"))
      (node (ref "C26") (pin "2") (pinfunction "2_2") (pintype "passive"))
      (node (ref "C5") (pin "1") (pinfunction "1_1") (pintype "passive"))
      (node (ref "C6") (pin "1") (pinfunction "1_1") (pintype "passive"))
      (node (ref "C7") (pin "2") (pinfunction "2_2") (pintype "passive"))
      (node (ref "C8") (pin "2") (pinfunction "2_2") (pintype "passive"))
      (node (ref "L1") (pin "2") (pinfunction "2_2") (pintype "passive"))
      (node (ref "U1") (pin "4") (pinfunction "FB_4") (pintype "passive"))
      (node (ref "U2") (pin "1") (pinfunction "VIN_1") (pintype "passive"))
      (node (ref "U7") (pin "3") (pinfunction "VDD_3") (pintype "passive"))
      (node (ref "U8") (pin "1") (pinfunction "VCC_1") (pintype "passive"))
    )
    (net (code "27") (name "GND") (class "Default")
      (node (ref "C10") (pin "1") (pinfunction "1_1") (pintype "passive"))
      (node (ref "C11") (pin "1") (pinfunction "1_1") (pintype "passive"))
      (node (ref "C12") (pin "1") (pinfunction "1_1") (pintype "passive"))
      (node (ref "C13") (pin "1") (pinfunction "1_1") (pintype "passive"))
      (node (ref "C14") (pin "1") (pinfunction "1_1") (pintype "passive"))
      (node (ref "C15") (pin "1") (pinfunction "1_1") (pintype "passive"))
      (node (ref "C16") (pin "2") (pinfunction "2_2") (pintype "passive"))
      (node (ref "C17") (pin "2") (pinfunction "2_2") (pintype "passive"))
      (node (ref "C18") (pin "1") (pinfunction "1_1") (pintype "passive"))
      (node (ref "C19") (pin "1") (pinfunction "1_1") (pintype "passive"))
      (node (ref "C2") (pin "2") (pinfunction "2_2") (pintype "passive"))
      (node (ref "C20") (pin "1") (pinfunction "1_1") (pintype "passive"))
      (node (ref "C22") (pin "1") (pinfunction "1_1") (pintype "passive"))
      (node (ref "C23") (pin "1") (pinfunction "1_1") (pintype "passive"))
      (node (ref "C24") (pin "1") (pinfunction "1_1") (pintype "passive"))
      (node (ref "C25") (pin "1") (pinfunction "1_1") (pintype "passive"))
      (node (ref "C26") (pin "1") (pinfunction "1_1") (pintype "passive"))
      (node (ref "C27") (pin "1") (pinfunction "1_1") (pintype "passive"))
      (node (ref "C29") (pin "1") (pinfunction "1_1") (pintype "passive"))
      (node (ref "C3") (pin "1") (pinfunction "1_1") (pintype "passive"))
      (node (ref "C30") (pin "2") (pinfunction "2_2") (pintype "passive"))
      (node (ref "C4") (pin "1") (pinfunction "1_1") (pintype "passive"))
      (node (ref "C5") (pin "2") (pinfunction "2_2") (pintype "passive"))
      (node (ref "C6") (pin "2") (pinfunction "2_2") (pintype "passive"))
      (node (ref "C7") (pin "1") (pinfunction "1_1") (pintype "passive"))
      (node (ref "C8") (pin "1") (pinfunction "1_1") (pintype "passive"))
      (node (ref "C9") (pin "2") (pinfunction "2_2") (pintype "passive"))
      (node (ref "D2") (pin "2") (pinfunction "A_2") (pintype "passive"))
      (node (ref "D4") (pin "2") (pinfunction "A_2") (pintype "passive"))
      (node (ref "D6") (pin "2") (pinfunction "K_2") (pintype "passive"))
      (node (ref "D7") (pin "3") (pinfunction "3_3") (pintype "passive"))
      (node (ref "J2") (pin "2") (pinfunction "2_2") (pintype "passive"))
      (node (ref "J3") (pin "2") (pinfunction "2_2") (pintype "passive"))
      (node (ref "P1") (pin "2") (pinfunction "2_2") (pintype "passive"))
      (node (ref "P2") (pin "3") (pinfunction "3_3") (pintype "passive"))
      (node (ref "P3") (pin "3") (pinfunction "3_3") (pintype "passive"))
      (node (ref "P6") (pin "12") (pinfunction "GND/Case_12") (pintype "passive"))
      (node (ref "P6") (pin "3") (pinfunction "VSS_3") (pintype "passive"))
      (node (ref "P6") (pin "6") (pinfunction "VSS_6") (pintype "passive"))
      (node (ref "R2") (pin "2") (pinfunction "2_2") (pintype "passive"))
      (node (ref "R9") (pin "2") (pinfunction "2_2") (pintype "passive"))
      (node (ref "S1") (pin "2") (pinfunction "2_2") (pintype "passive"))
      (node (ref "U1") (pin "3") (pinfunction "SGND_3") (pintype "passive"))
      (node (ref "U1") (pin "6") (pinfunction "GND_6") (pintype "passive"))
      (node (ref "U2") (pin "4") (pinfunction "SD_4") (pintype "passive"))
      (node (ref "U2") (pin "5") (pinfunction "GND_5") (pintype "passive"))
      (node (ref "U2") (pin "6") (pinfunction "GND_6") (pintype "passive"))
      (node (ref "U2") (pin "7") (pinfunction "GND_7") (pintype "passive"))
      (node (ref "U2") (pin "8") (pinfunction "GND_8") (pintype "passive"))
      (node (ref "U3") (pin "3") (pinfunction "GND_3") (pintype "passive"))
      (node (ref "U4") (pin "16") (pinfunction "AVSS_16") (pintype "passive"))
      (node (ref "U4") (pin "30") (pinfunction "VSS_30") (pintype "passive"))
      (node (ref "U4") (pin "39") (pinfunction "VSS_39") (pintype "passive"))
      (node (ref "U4") (pin "6") (pinfunction "VSS_6") (pintype "passive"))
      (node (ref "U5") (pin "2") (pinfunction "2_2") (pintype "passive"))
      (node (ref "U5") (pin "5") (pinfunction "5_5") (pintype "passive"))
      (node (ref "U6") (pin "2") (pinfunction "2_2") (pintype "passive"))
      (node (ref "U6") (pin "5") (pinfunction "5_5") (pintype "passive"))
      (node (ref "U7") (pin "2") (pinfunction "VSS_2") (pintype "passive"))
      (node (ref "U7") (pin "8") (pinfunction "STBY_8") (pintype "passive"))
      (node (ref "U8") (pin "4") (pinfunction "GND_4") (pintype "passive"))
      (node (ref "Y1") (pin "2") (pinfunction "2_2") (pintype "passive"))
      (node (ref "Y1") (pin "4") (pinfunction "4_4") (pintype "passive"))
    )
    (net (code "28") (name "Net-(C16-Pad1)") (class "Default")
      (node (ref "C16") (pin "1") (pinfunction "1_1") (pintype "passive"))
      (node (ref "P2") (pin "1") (pinfunction "1_1") (pintype "passive"))
      (node (ref "R6") (pin "2") (pinfunction "2_2") (pintype "passive"))
      (node (ref "R8") (pin "2") (pinfunction "2_2") (pintype "passive"))
    )
    (net (code "29") (name "Net-(C23-Pad2)") (class "Default")
      (node (ref "C23") (pin "2") (pinfunction "2_2") (pintype "passive"))
      (node (ref "R15") (pin "2") (pinfunction "2_2") (pintype "passive"))
      (node (ref "R16") (pin "2") (pinfunction "2_2") (pintype "passive"))
      (node (ref "S1") (pin "1") (pinfunction "1_1") (pintype "passive"))
    )
    (net (code "30") (name "Net-(C29-Pad2)") (class "Default")
      (node (ref "C29") (pin "2") (pinfunction "2_2") (pintype "passive"))
      (node (ref "R20") (pin "2") (pinfunction "2_2") (pintype "passive"))
      (node (ref "R28") (pin "1") (pinfunction "1_1") (pintype "passive"))
    )
    (net (code "31") (name "Net-(D1-A)") (class "Default")
      (node (ref "D1") (pin "2") (pinfunction "A_2") (pintype "passive"))
      (node (ref "P1") (pin "1") (pinfunction "1_1") (pintype "passive"))
    )
    (net (code "32") (name "Net-(D2-K)") (class "Default")
      (node (ref "C1") (pin "1") (pinfunction "1_1") (pintype "passive"))
      (node (ref "D2") (pin "1") (pinfunction "K_1") (pintype "passive"))
      (node (ref "L1") (pin "1") (pinfunction "1_1") (pintype "passive"))
      (node (ref "U1") (pin "8") (pinfunction "LX_8") (pintype "passive"))
    )
    (net (code "33") (name "Net-(D3-A)") (class "Default")
      (node (ref "D3") (pin "2") (pinfunction "A_2") (pintype "passive"))
      (node (ref "J1") (pin "2") (pinfunction "2_2") (pintype "passive"))
    )
    (net (code "34") (name "Net-(D3-K)") (class "Default")
      (node (ref "D3") (pin "1") (pinfunction "K_1") (pintype "passive"))
      (node (ref "F1") (pin "1") (pinfunction "1_1") (pintype "passive"))
    )
    (net (code "35") (name "Net-(D4-K)") (class "Default")
      (node (ref "D4") (pin "1") (pinfunction "K_1") (pintype "passive"))
      (node (ref "L2") (pin "1") (pinfunction "1_1") (pintype "passive"))
      (node (ref "U2") (pin "2") (pinfunction "OUT_2") (pintype "passive"))
    )
    (net (code "36") (name "Net-(D6-A_G)") (class "Default")
      (node (ref "D6") (pin "3") (pinfunction "A_G_3") (pintype "passive"))
      (node (ref "R14") (pin "2") (pinfunction "2_2") (pintype "passive"))
    )
    (net (code "37") (name "Net-(D6-A_R)") (class "Default")
      (node (ref "D6") (pin "1") (pinfunction "A_R_1") (pintype "passive"))
      (node (ref "R13") (pin "2") (pinfunction "2_2") (pintype "passive"))
    )
    (net (code "38") (name "Net-(P3-Pad1)") (class "Default")
      (node (ref "P3") (pin "1") (pinfunction "1_1") (pintype "passive"))
      (node (ref "R10") (pin "2") (pinfunction "2_2") (pintype "passive"))
    )
    (net (code "39") (name "Net-(P3-Pad2)") (class "Default")
      (node (ref "P3") (pin "2") (pinfunction "2_2") (pintype "passive"))
      (node (ref "R11") (pin "2") (pinfunction "2_2") (pintype "passive"))
    )
    (net (code "40") (name "Net-(P4-Pad1)") (class "Default")
      (node (ref "P4") (pin "1") (pinfunction "1_1") (pintype "passive"))
      (node (ref "P5") (pin "1") (pinfunction "1_1") (pintype "passive"))
    )
    (net (code "41") (name "Net-(P4-Pad2)") (class "Default")
      (node (ref "P4") (pin "2") (pinfunction "2_2") (pintype "passive"))
      (node (ref "P5") (pin "2") (pinfunction "2_2") (pintype "passive"))
    )
    (net (code "42") (name "Net-(P4-Pad4)") (class "Default")
      (node (ref "P4") (pin "4") (pinfunction "4_4") (pintype "passive"))
      (node (ref "P5") (pin "4") (pinfunction "4_4") (pintype "passive"))
    )
    (net (code "43") (name "Net-(P4-Pad5)") (class "Default")
      (node (ref "P4") (pin "5") (pinfunction "5_5") (pintype "passive"))
      (node (ref "P5") (pin "5") (pinfunction "5_5") (pintype "passive"))
    )
    (net (code "44") (name "Net-(P6-CD{slash}DAT3)") (class "Default")
      (node (ref "P6") (pin "1") (pinfunction "CD/DAT3_1") (pintype "passive"))
      (node (ref "U5") (pin "3") (pinfunction "3_3") (pintype "passive"))
    )
    (net (code "45") (name "Net-(P6-CLK)") (class "Default")
      (node (ref "P6") (pin "5") (pinfunction "CLK_5") (pintype "passive"))
      (node (ref "U6") (pin "6") (pinfunction "6_6") (pintype "passive"))
    )
    (net (code "46") (name "Net-(P6-CMD)") (class "Default")
      (node (ref "P6") (pin "2") (pinfunction "CMD_2") (pintype "passive"))
      (node (ref "U5") (pin "6") (pinfunction "6_6") (pintype "passive"))
    )
    (net (code "47") (name "Net-(P6-DAT0)") (class "Default")
      (node (ref "P6") (pin "7") (pinfunction "DAT0_7") (pintype "passive"))
      (node (ref "U6") (pin "3") (pinfunction "3_3") (pintype "passive"))
    )
    (net (code "48") (name "Net-(P6-Detect)") (class "Default")
      (node (ref "P6") (pin "10") (pinfunction "Detect_10") (pintype "passive"))
      (node (ref "R27") (pin "2") (pinfunction "2_2") (pintype "passive"))
      (node (ref "R29") (pin "1") (pinfunction "1_1") (pintype "passive"))
    )
    (net (code "49") (name "Net-(P6-Protect)") (class "Default")
      (node (ref "P6") (pin "11") (pinfunction "Protect_11") (pintype "passive"))
      (node (ref "R23") (pin "2") (pinfunction "2_2") (pintype "passive"))
      (node (ref "R24") (pin "1") (pinfunction "1_1") (pintype "passive"))
    )
    (net (code "50") (name "Net-(U1-BST)") (class "Default")
      (node (ref "C1") (pin "2") (pinfunction "2_2") (pintype "passive"))
      (node (ref "U1") (pin "1") (pinfunction "BST_1") (pintype "passive"))
    )
    (net (code "51") (name "Net-(U1-ON{slash}~{OFF})") (class "Default")
      (node (ref "R1") (pin "2") (pinfunction "2_2") (pintype "passive"))
      (node (ref "R2") (pin "1") (pinfunction "1_1") (pintype "passive"))
      (node (ref "U1") (pin "5") (pinfunction "ON/~{OFF}_5") (pintype "passive"))
    )
    (net (code "52") (name "Net-(U1-VD)") (class "Default")
      (node (ref "C11") (pin "2") (pinfunction "2_2") (pintype "passive"))
      (node (ref "U1") (pin "2") (pinfunction "VD_2") (pintype "passive"))
    )
    (net (code "53") (name "Net-(U3-VDD)") (class "Default")
      (node (ref "R3") (pin "2") (pinfunction "2_2") (pintype "passive"))
      (node (ref "R9") (pin "1") (pinfunction "1_1") (pintype "passive"))
      (node (ref "U3") (pin "2") (pinfunction "VDD_2") (pintype "passive"))
    )
    (net (code "54") (name "Net-(U3-Vout)") (class "Default")
      (node (ref "C17") (pin "1") (pinfunction "1_1") (pintype "passive"))
      (node (ref "R5") (pin "2") (pinfunction "2_2") (pintype "passive"))
      (node (ref "R7") (pin "1") (pinfunction "1_1") (pintype "passive"))
      (node (ref "U3") (pin "1") (pinfunction "Vout_1") (pintype "passive"))
    )
    (net (code "55") (name "Net-(U4-OSC2{slash}CLKO{slash}AN7{slash}CMP3D{slash}CMP4B{slash}PGA1N2{slash}RP34{slash}RB2)") (class "Default")
      (node (ref "C13") (pin "2") (pinfunction "2_2") (pintype "passive"))
      (node (ref "R4") (pin "2") (pinfunction "2_2") (pintype "passive"))
      (node (ref "U4") (pin "33") (pinfunction "OSC2/CLKO/AN7/CMP3D/CMP4B/PGA1N2/RP34/RB2_33") (pintype "passive"))
      (node (ref "Y1") (pin "3") (pinfunction "3_3") (pintype "passive"))
    )
    (net (code "56") (name "Net-(U4-OSCI{slash}CLKI{slash}AN6{slash}CMP3C{slash}CMP4A{slash}ISRC2{slash}RP33{slash}RB1)") (class "Default")
      (node (ref "C12") (pin "2") (pinfunction "2_2") (pintype "passive"))
      (node (ref "R4") (pin "1") (pinfunction "1_1") (pintype "passive"))
      (node (ref "U4") (pin "32") (pinfunction "OSCI/CLKI/AN6/CMP3C/CMP4A/ISRC2/RP33/RB1_32") (pintype "passive"))
      (node (ref "Y1") (pin "1") (pinfunction "1_1") (pintype "passive"))
    )
    (net (code "57") (name "Net-(U4-VCAP)") (class "Default")
      (node (ref "C20") (pin "2") (pinfunction "2_2") (pintype "passive"))
      (node (ref "U4") (pin "7") (pinfunction "VCAP_7") (pintype "passive"))
    )
    (net (code "58") (name "Net-(U7-CANH)") (class "Default")
      (node (ref "C27") (pin "2") (pinfunction "2_2") (pintype "passive"))
      (node (ref "L3") (pin "3") (pinfunction "3_3") (pintype "passive"))
      (node (ref "R20") (pin "1") (pinfunction "1_1") (pintype "passive"))
      (node (ref "U7") (pin "7") (pinfunction "CANH_7") (pintype "passive"))
    )
    (net (code "59") (name "Net-(U7-CANL)") (class "Default")
      (node (ref "C30") (pin "1") (pinfunction "1_1") (pintype "passive"))
      (node (ref "L3") (pin "2") (pinfunction "2_2") (pintype "passive"))
      (node (ref "R28") (pin "2") (pinfunction "2_2") (pintype "passive"))
      (node (ref "U7") (pin "6") (pinfunction "CANL_6") (pintype "passive"))
    )
    (net (code "60") (name "Net-(U7-RXD)") (class "Default")
      (node (ref "R25") (pin "1") (pinfunction "1_1") (pintype "passive"))
      (node (ref "U7") (pin "4") (pinfunction "RXD_4") (pintype "passive"))
    )
    (net (code "61") (name "Net-(U7-TXD)") (class "Default")
      (node (ref "R21") (pin "1") (pinfunction "1_1") (pintype "passive"))
      (node (ref "U7") (pin "1") (pinfunction "TXD_1") (pintype "passive"))
    )
    (net (code "62") (name "Net-(U8-RX)") (class "Default")
      (node (ref "R22") (pin "2") (pinfunction "2_2") (pintype "passive"))
      (node (ref "U8") (pin "2") (pinfunction "RX_2") (pintype "passive"))
    )
    (net (code "63") (name "Net-(U8-TX)") (class "Default")
      (node (ref "R26") (pin "2") (pinfunction "2_2") (pintype "passive"))
      (node (ref "U8") (pin "3") (pinfunction "TX_3") (pintype "passive"))
    )
    (net (code "64") (name "Vin") (class "Default")
      (node (ref "C2") (pin "1") (pinfunction "1_1") (pintype "passive"))
      (node (ref "C3") (pin "2") (pinfunction "2_2") (pintype "passive"))
      (node (ref "C4") (pin "2") (pinfunction "2_2") (pintype "passive"))
      (node (ref "D1") (pin "1") (pinfunction "K_1") (pintype "passive"))
      (node (ref "F1") (pin "2") (pinfunction "2_2") (pintype "passive"))
      (node (ref "R1") (pin "1") (pinfunction "1_1") (pintype "passive"))
      (node (ref "R3") (pin "1") (pinfunction "1_1") (pintype "passive"))
      (node (ref "U1") (pin "7") (pinfunction "VIN_7") (pintype "passive"))
    )
    (net (code "65") (name "unconnected-(P2-Pad6)") (class "Default")
      (node (ref "P2") (pin "6") (pinfunction "6_6") (pintype "passive"))
    )
    (net (code "66") (name "unconnected-(P6-DAT1-Pad8)") (class "Default")
      (node (ref "P6") (pin "8") (pinfunction "DAT1_8") (pintype "passive"))
    )
    (net (code "67") (name "unconnected-(P6-DAT2-Pad9)") (class "Default")
      (node (ref "P6") (pin "9") (pinfunction "DAT2_9") (pintype "passive"))
    )
    (net (code "68") (name "unconnected-(U4-AN0ALT{slash}RP53{slash}RC5-Pad3)") (class "Default")
      (node (ref "U4") (pin "3") (pinfunction "AN0ALT/RP53/RC5_3") (pintype "passive"))
    )
    (net (code "69") (name "unconnected-(U4-AN1ALT{slash}RP52{slash}RC4-Pad2)") (class "Default")
      (node (ref "U4") (pin "2") (pinfunction "AN1ALT/RP52/RC4_2") (pintype "passive"))
    )
    (net (code "70") (name "unconnected-(U4-AN11{slash}PGA1N3{slash}RP57{slash}RC9-Pad27)") (class "Default")
      (node (ref "U4") (pin "27") (pinfunction "AN11/PGA1N3/RP57/RC9_27") (pintype "passive"))
    )
    (net (code "71") (name "unconnected-(U4-AN14{slash}PGA2N3{slash}RP60{slash}RC12-Pad20)") (class "Default")
      (node (ref "U4") (pin "20") (pinfunction "AN14/PGA2N3/RP60/RC12_20") (pintype "passive"))
    )
    (net (code "72") (name "unconnected-(U4-AN17{slash}RP54{slash}RC6-Pad4)") (class "Default")
      (node (ref "U4") (pin "4") (pinfunction "AN17/RP54/RC6_4") (pintype "passive"))
    )
    (net (code "73") (name "unconnected-(U4-ASCL1{slash}RP56{slash}RC8-Pad38)") (class "Default")
      (node (ref "U4") (pin "38") (pinfunction "ASCL1/RP56/RC8_38") (pintype "passive"))
    )
    (net (code "74") (name "unconnected-(U4-FLT11{slash}RP61{slash}RC13-Pad15)") (class "Default")
      (node (ref "U4") (pin "15") (pinfunction "FLT11/RP61/RC13_15") (pintype "passive"))
    )
    (net (code "75") (name "unconnected-(U4-FLT12{slash}RP48{slash}RC0-Pad14)") (class "Default")
      (node (ref "U4") (pin "14") (pinfunction "FLT12/RP48/RC0_14") (pintype "passive"))
    )
    (net (code "76") (name "unconnected-(U4-PGEC3{slash}SCL2{slash}RP47{slash}RB15-Pad42)") (class "Default")
      (node (ref "U4") (pin "42") (pinfunction "PGEC3/SCL2/RP47/RB15_42") (pintype "passive"))
    )
    (net (code "77") (name "unconnected-(U4-PGED3{slash}SDA2{slash}FLT31{slash}RP40{slash}RB8-Pad41)") (class "Default")
      (node (ref "U4") (pin "41") (pinfunction "PGED3/SDA2/FLT31/RP40/RB8_41") (pintype "passive"))
    )
    (net (code "78") (name "unconnected-(U4-RP51{slash}RC3-Pad5)") (class "Default")
      (node (ref "U4") (pin "5") (pinfunction "RP51/RC3_5") (pintype "passive"))
    )
    (net (code "79") (name "unconnected-(U4-TDO{slash}AN19{slash}PGA2N2{slash}RP37{slash}RB5-Pad43)") (class "Default")
      (node (ref "U4") (pin "43") (pinfunction "TDO/AN19/PGA2N2/RP37/RB5_43") (pintype "passive"))
    )
    (net (code "80") (name "unconnected-(U4-TMS{slash}PWM3H{slash}RP43{slash}RB11-Pad8)") (class "Default")
      (node (ref "U4") (pin "8") (pinfunction "TMS/PWM3H/RP43/RB11_8") (pintype "passive"))
    )
  )
)
